# SoC_PS_500_501_502_MIO.net
KiCad netlist of a schematic drawn in Altium Designer
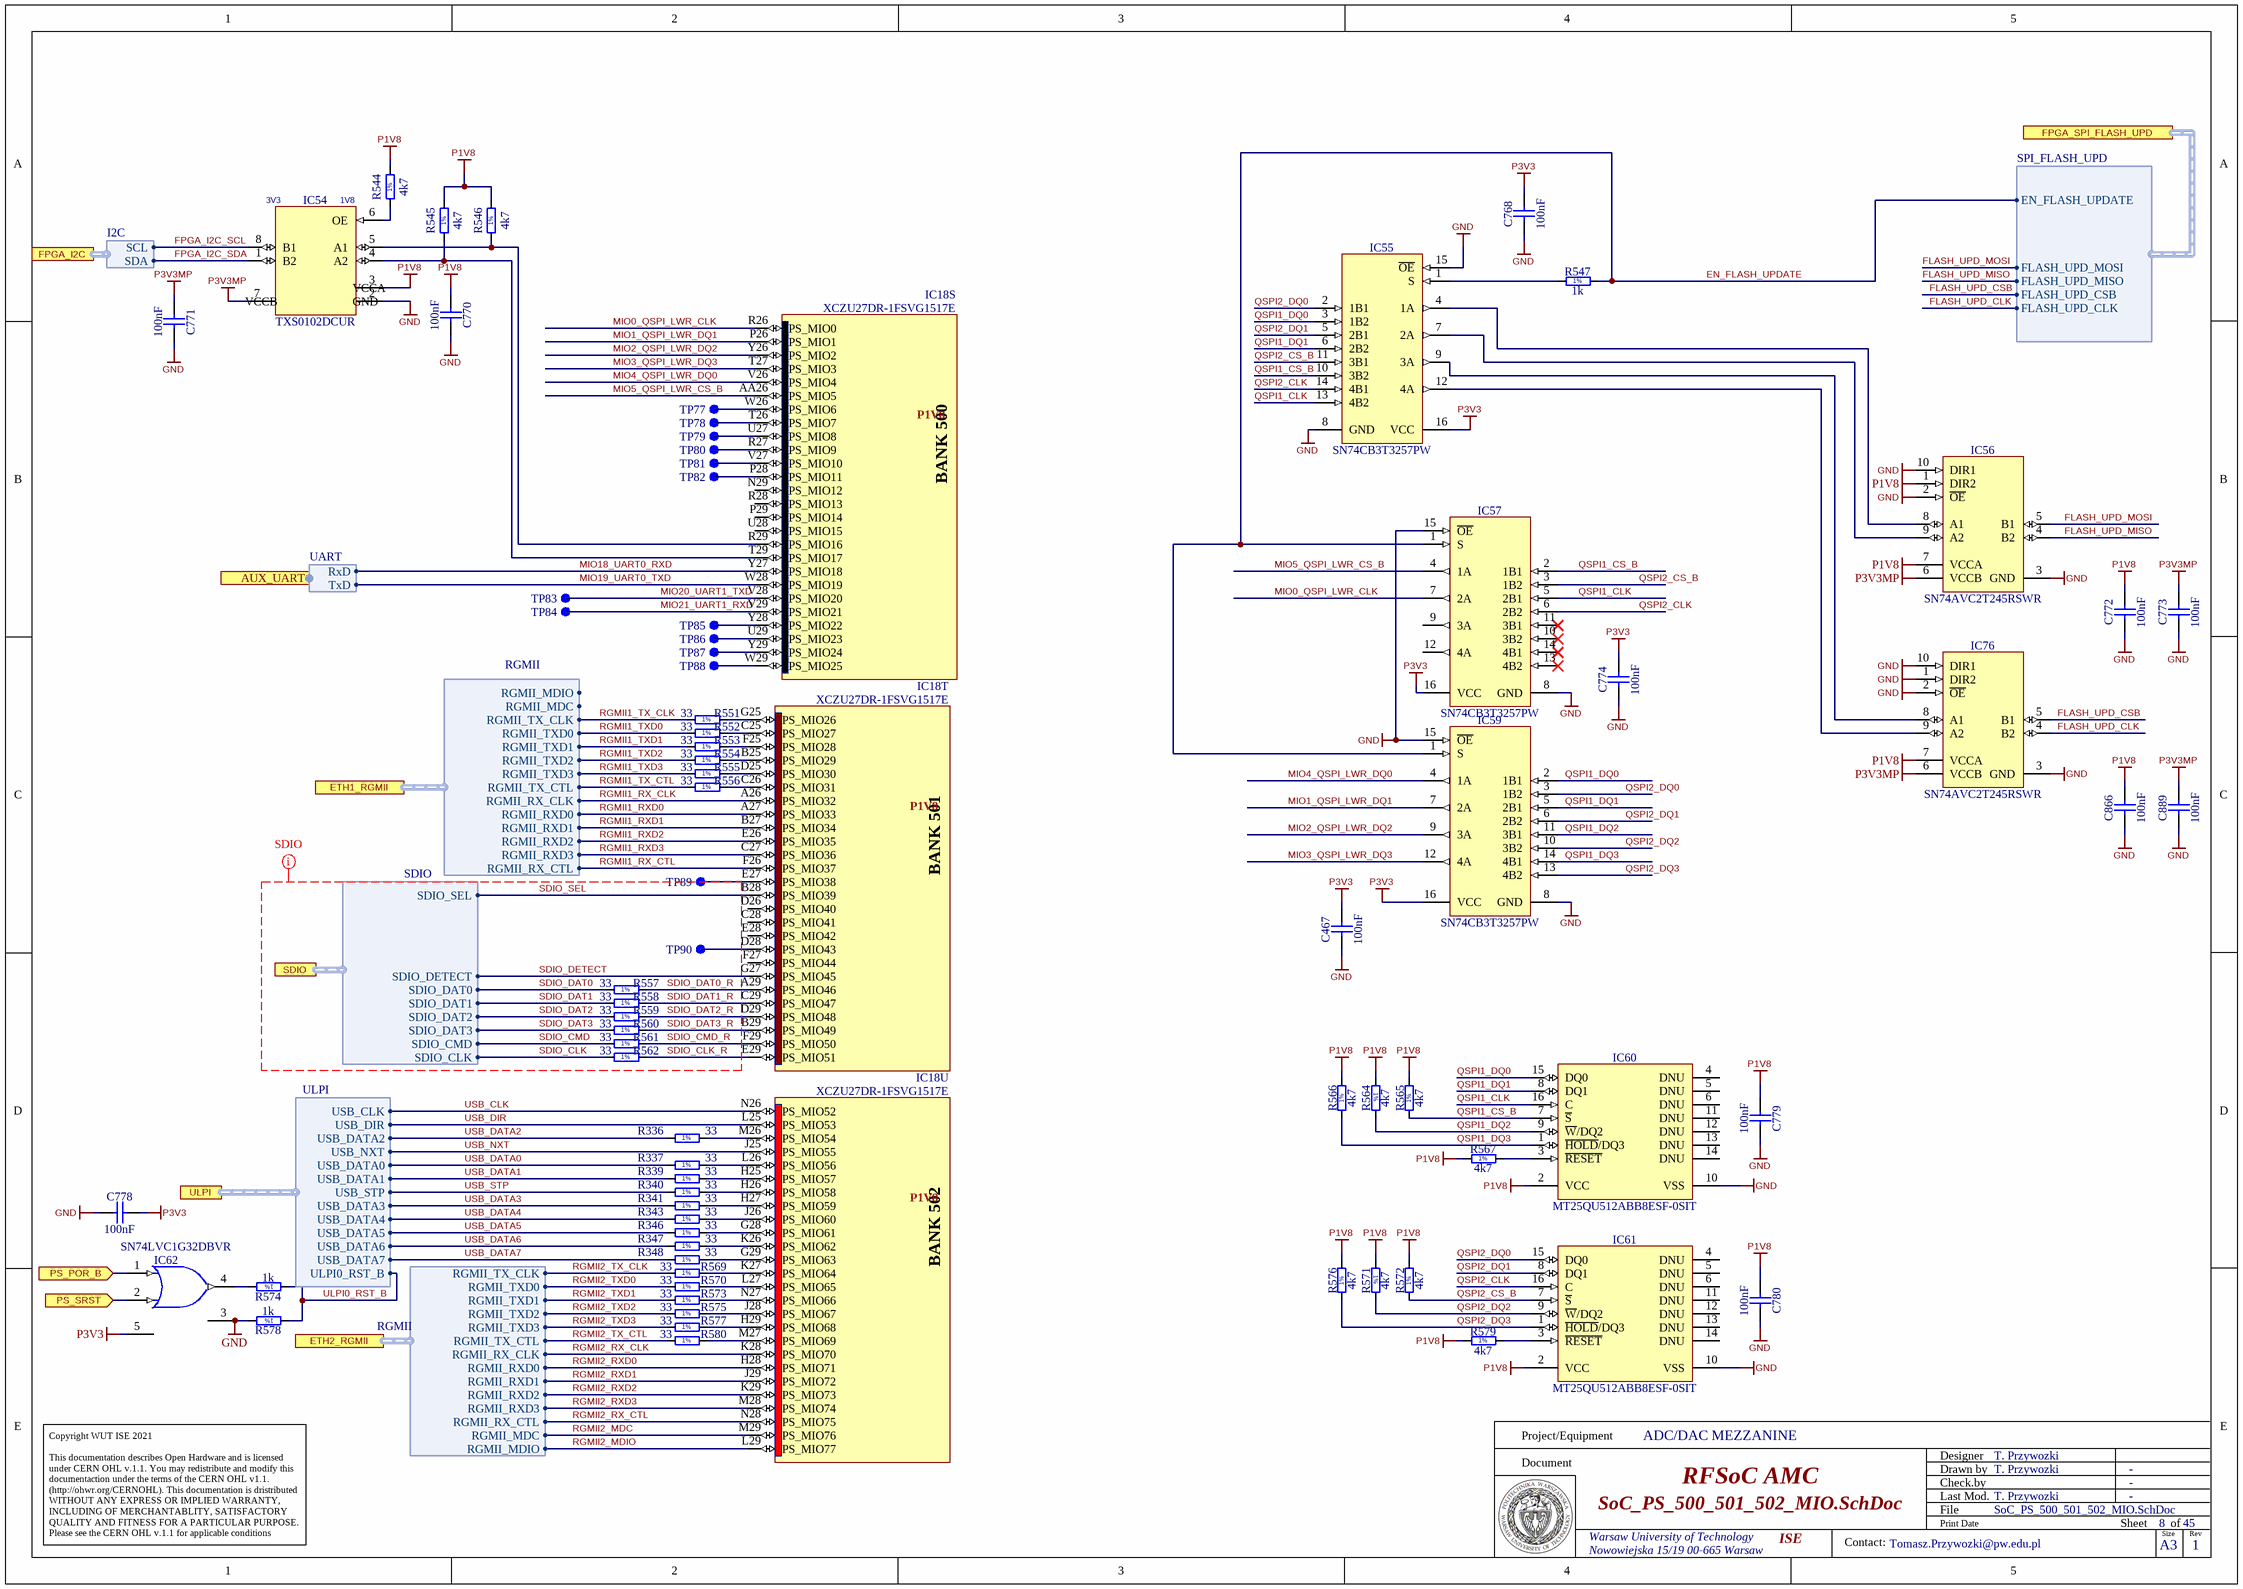
[diagram p0: SoC_PS_500_501_502_MIO.SchDoc]

(export (version "E")
  (design (tool "Eeschema 10.0.6"))
  (components
    (comp (ref "C467")
      (value "100nF")
      (footprint "CAPC0603X33N")
      (description "Non-polarised capacitor")
      (fields
        (field (name "MANUFACTURER PART NUMBER") "CC0201_100NF_6.3V_10%_X5R")
        (field (name "MANUFACTURER") "GENERIC")
        (field (name "AUTHOR") "CERN DEM JLC")
      )
      (libsource (lib "Capacitors") (part "Capacitor - non polarized"))
    )
    (comp (ref "C768")
      (value "100nF")
      (footprint "CAPC0603X33N")
      (description "Non-polarised capacitor")
      (fields
        (field (name "MANUFACTURER PART NUMBER") "CC0201_100NF_6.3V_10%_X5R")
        (field (name "MANUFACTURER") "GENERIC")
        (field (name "AUTHOR") "CERN DEM JLC")
      )
      (libsource (lib "Capacitors") (part "Capacitor - non polarized"))
    )
    (comp (ref "C770")
      (value "100nF")
      (footprint "CAPC0603X33N")
      (description "Non-polarised capacitor")
      (fields
        (field (name "MANUFACTURER PART NUMBER") "CC0201_100NF_6.3V_10%_X5R")
        (field (name "MANUFACTURER") "GENERIC")
        (field (name "AUTHOR") "CERN DEM JLC")
      )
      (libsource (lib "Capacitors") (part "Capacitor - non polarized"))
    )
    (comp (ref "C771")
      (value "100nF")
      (footprint "CAPC0603X33N")
      (description "Non-polarised capacitor")
      (fields
        (field (name "MANUFACTURER PART NUMBER") "CC0201_100NF_6.3V_10%_X5R")
        (field (name "MANUFACTURER") "GENERIC")
        (field (name "AUTHOR") "CERN DEM JLC")
      )
      (libsource (lib "Capacitors") (part "Capacitor - non polarized"))
    )
    (comp (ref "C772")
      (value "100nF")
      (footprint "CAPC0603X33N")
      (description "Non-polarised capacitor")
      (fields
        (field (name "MANUFACTURER PART NUMBER") "CC0201_100NF_6.3V_10%_X5R")
        (field (name "MANUFACTURER") "GENERIC")
        (field (name "AUTHOR") "CERN DEM JLC")
      )
      (libsource (lib "Capacitors") (part "Capacitor - non polarized"))
    )
    (comp (ref "C773")
      (value "100nF")
      (footprint "CAPC0603X33N")
      (description "Non-polarised capacitor")
      (fields
        (field (name "MANUFACTURER PART NUMBER") "CC0201_100NF_6.3V_10%_X5R")
        (field (name "MANUFACTURER") "GENERIC")
        (field (name "AUTHOR") "CERN DEM JLC")
      )
      (libsource (lib "Capacitors") (part "Capacitor - non polarized"))
    )
    (comp (ref "C774")
      (value "100nF")
      (footprint "CAPC0603X33N")
      (description "Non-polarised capacitor")
      (fields
        (field (name "MANUFACTURER PART NUMBER") "CC0201_100NF_6.3V_10%_X5R")
        (field (name "MANUFACTURER") "GENERIC")
        (field (name "AUTHOR") "CERN DEM JLC")
      )
      (libsource (lib "Capacitors") (part "Capacitor - non polarized"))
    )
    (comp (ref "C778")
      (value "100nF")
      (footprint "CAPC0603X33N")
      (description "Non-polarised capacitor")
      (fields
        (field (name "MANUFACTURER PART NUMBER") "CC0201_100NF_6.3V_10%_X5R")
        (field (name "MANUFACTURER") "GENERIC")
        (field (name "AUTHOR") "CERN DEM JLC")
      )
      (libsource (lib "Capacitors") (part "Capacitor - non polarized"))
    )
    (comp (ref "C779")
      (value "100nF")
      (footprint "CAPC0603X33N")
      (description "Non-polarised capacitor")
      (fields
        (field (name "MANUFACTURER PART NUMBER") "CC0201_100NF_6.3V_10%_X5R")
        (field (name "MANUFACTURER") "GENERIC")
        (field (name "AUTHOR") "CERN DEM JLC")
      )
      (libsource (lib "Capacitors") (part "Capacitor - non polarized"))
    )
    (comp (ref "C780")
      (value "100nF")
      (footprint "CAPC0603X33N")
      (description "Non-polarised capacitor")
      (fields
        (field (name "MANUFACTURER PART NUMBER") "CC0201_100NF_6.3V_10%_X5R")
        (field (name "MANUFACTURER") "GENERIC")
        (field (name "AUTHOR") "CERN DEM JLC")
      )
      (libsource (lib "Capacitors") (part "Capacitor - non polarized"))
    )
    (comp (ref "C866")
      (value "100nF")
      (footprint "CAPC0603X33N")
      (description "Non-polarised capacitor")
      (fields
        (field (name "MANUFACTURER PART NUMBER") "CC0201_100NF_6.3V_10%_X5R")
        (field (name "MANUFACTURER") "GENERIC")
        (field (name "AUTHOR") "CERN DEM JLC")
      )
      (libsource (lib "Capacitors") (part "Capacitor - non polarized"))
    )
    (comp (ref "C889")
      (value "100nF")
      (footprint "CAPC0603X33N")
      (description "Non-polarised capacitor")
      (fields
        (field (name "MANUFACTURER PART NUMBER") "CC0201_100NF_6.3V_10%_X5R")
        (field (name "MANUFACTURER") "GENERIC")
        (field (name "AUTHOR") "CERN DEM JLC")
      )
      (libsource (lib "Capacitors") (part "Capacitor - non polarized"))
    )
    (comp (ref "IC18")
      (value "XCZU27DR-1FSVG1517E")
      (footprint "XILINX_FSVG1517 (XCZU27DR)")
      (fields (field (name "MANUFACTURER") "XILINX") (field (name "AUTHOR") "CERN DEM MR"))
      (libsource (lib "ICs And Semiconductors") (part "XCZU27DR-1FSVG1517E"))
    )
    (comp (ref "IC54")
      (value "TXS0102DCUR")
      (footprint "SOP50P310X90-8N")
      (description "2-Bit Bidirectionnal Voltage-Level Translator for Open-Drain And Push-Pull Applications")
      (fields (field (name "MANUFACTURER") "TEXAS INSTRUMENTS") (field (name "AUTHOR") "CERN DEM JLC"))
      (libsource (lib "ICs And Semiconductors") (part "TXS0102DCU"))
    )
    (comp (ref "IC55")
      (value "SN74CB3T3257PW")
      (footprint "SOP65P640X120-16N")
      (description "4-BIT 1-OF-2 FET Multiplexer/Demultiplexer 2.5V/3.3V Low-Voltage Bus Switch 5V Tolerant Shifter")
      (fields (field (name "MANUFACTURER") "TEXAS INSTRUMENTS") (field (name "AUTHOR") "CERN DEM JLC"))
      (libsource (lib "ICs And Semiconductors") (part "743257"))
    )
    (comp (ref "IC56")
      (value "SN74AVC2T245RSWR")
      (footprint "QFN40P140X180X55-10N")
      (description "Dual-Bit Dual-Supply Bus Transceiver With Configurable Voltage Translation and 3-State Outputs")
      (fields (field (name "MANUFACTURER") "TEXAS INSTRUMENTS") (field (name "AUTHOR") "CERN DEM JLC"))
      (libsource (lib "ICs And Semiconductors") (part "742T245"))
    )
    (comp (ref "IC57")
      (value "SN74CB3T3257PW")
      (footprint "SOP65P640X120-16N")
      (description "4-BIT 1-OF-2 FET Multiplexer/Demultiplexer 2.5V/3.3V Low-Voltage Bus Switch 5V Tolerant Shifter")
      (fields (field (name "MANUFACTURER") "TEXAS INSTRUMENTS") (field (name "AUTHOR") "CERN DEM JLC"))
      (libsource (lib "") (part "743257_1"))
    )
    (comp (ref "IC59")
      (value "SN74CB3T3257PW")
      (footprint "SOP65P640X120-16N")
      (description "4-BIT 1-OF-2 FET Multiplexer/Demultiplexer 2.5V/3.3V Low-Voltage Bus Switch 5V Tolerant Shifter")
      (fields (field (name "MANUFACTURER") "TEXAS INSTRUMENTS") (field (name "AUTHOR") "CERN DEM JLC"))
      (libsource (lib "") (part "743257_1"))
    )
    (comp (ref "IC60")
      (value "MT25QU512ABB8ESF-0SIT")
      (footprint "SOIC127P1030X265-16N")
      (description "512Mbit (64MB), 1.8V, Multiple I/O Serial Flash Memory, Reset# & Hold# Pins")
      (fields (field (name "MANUFACTURER") "MICRON TECHNOLOGY") (field (name "AUTHOR") "CERN DEM MR"))
      (libsource (lib "ICs And Semiconductors") (part "MT25QU512ABB8ESF"))
    )
    (comp (ref "IC61")
      (value "MT25QU512ABB8ESF-0SIT")
      (footprint "SOIC127P1030X265-16N")
      (description "512Mbit (64MB), 1.8V, Multiple I/O Serial Flash Memory, Reset# & Hold# Pins")
      (fields (field (name "MANUFACTURER") "MICRON TECHNOLOGY") (field (name "AUTHOR") "CERN DEM MR"))
      (libsource (lib "ICs And Semiconductors") (part "MT25QU512ABB8ESF"))
    )
    (comp (ref "IC62")
      (value "SN74LVC1G32DBVR")
      (footprint "SOT95P280X145-5N")
      (description "Single 2-Input Positive-OR Gate")
      (fields (field (name "MANUFACTURER") "TEXAS INSTRUMENTS") (field (name "AUTHOR") "CERN DEM JLC"))
      (libsource (lib "ICs And Semiconductors") (part "741G32"))
    )
    (comp (ref "IC76")
      (value "SN74AVC2T245RSWR")
      (footprint "QFN40P140X180X55-10N")
      (description "Dual-Bit Dual-Supply Bus Transceiver With Configurable Voltage Translation and 3-State Outputs")
      (fields (field (name "MANUFACTURER") "TEXAS INSTRUMENTS") (field (name "AUTHOR") "CERN DEM JLC"))
      (libsource (lib "ICs And Semiconductors") (part "742T245"))
    )
    (comp (ref "R336")
      (value "33")
      (footprint "RESC1005X40N")
      (description "Resistor - 1%")
      (fields
        (field (name "MANUFACTURER PART NUMBER") "R0402_33R_1%_0.0625W_100PPM")
        (field (name "MANUFACTURER") "GENERIC")
        (field (name "AUTHOR") "CERN DEM JLC")
      )
      (libsource (lib "Resistors") (part "Resistor - 1%"))
    )
    (comp (ref "R337")
      (value "33")
      (footprint "RESC1005X40N")
      (description "Resistor - 1%")
      (fields
        (field (name "MANUFACTURER PART NUMBER") "R0402_33R_1%_0.0625W_100PPM")
        (field (name "MANUFACTURER") "GENERIC")
        (field (name "AUTHOR") "CERN DEM JLC")
      )
      (libsource (lib "Resistors") (part "Resistor - 1%"))
    )
    (comp (ref "R339")
      (value "33")
      (footprint "RESC1005X40N")
      (description "Resistor - 1%")
      (fields
        (field (name "MANUFACTURER PART NUMBER") "R0402_33R_1%_0.0625W_100PPM")
        (field (name "MANUFACTURER") "GENERIC")
        (field (name "AUTHOR") "CERN DEM JLC")
      )
      (libsource (lib "Resistors") (part "Resistor - 1%"))
    )
    (comp (ref "R340")
      (value "33")
      (footprint "RESC1005X40N")
      (description "Resistor - 1%")
      (fields
        (field (name "MANUFACTURER PART NUMBER") "R0402_33R_1%_0.0625W_100PPM")
        (field (name "MANUFACTURER") "GENERIC")
        (field (name "AUTHOR") "CERN DEM JLC")
      )
      (libsource (lib "Resistors") (part "Resistor - 1%"))
    )
    (comp (ref "R341")
      (value "33")
      (footprint "RESC1005X40N")
      (description "Resistor - 1%")
      (fields
        (field (name "MANUFACTURER PART NUMBER") "R0402_33R_1%_0.0625W_100PPM")
        (field (name "MANUFACTURER") "GENERIC")
        (field (name "AUTHOR") "CERN DEM JLC")
      )
      (libsource (lib "Resistors") (part "Resistor - 1%"))
    )
    (comp (ref "R343")
      (value "33")
      (footprint "RESC1005X40N")
      (description "Resistor - 1%")
      (fields
        (field (name "MANUFACTURER PART NUMBER") "R0402_33R_1%_0.0625W_100PPM")
        (field (name "MANUFACTURER") "GENERIC")
        (field (name "AUTHOR") "CERN DEM JLC")
      )
      (libsource (lib "Resistors") (part "Resistor - 1%"))
    )
    (comp (ref "R346")
      (value "33")
      (footprint "RESC1005X40N")
      (description "Resistor - 1%")
      (fields
        (field (name "MANUFACTURER PART NUMBER") "R0402_33R_1%_0.0625W_100PPM")
        (field (name "MANUFACTURER") "GENERIC")
        (field (name "AUTHOR") "CERN DEM JLC")
      )
      (libsource (lib "Resistors") (part "Resistor - 1%"))
    )
    (comp (ref "R347")
      (value "33")
      (footprint "RESC1005X40N")
      (description "Resistor - 1%")
      (fields
        (field (name "MANUFACTURER PART NUMBER") "R0402_33R_1%_0.0625W_100PPM")
        (field (name "MANUFACTURER") "GENERIC")
        (field (name "AUTHOR") "CERN DEM JLC")
      )
      (libsource (lib "Resistors") (part "Resistor - 1%"))
    )
    (comp (ref "R348")
      (value "33")
      (footprint "RESC1005X40N")
      (description "Resistor - 1%")
      (fields
        (field (name "MANUFACTURER PART NUMBER") "R0402_33R_1%_0.0625W_100PPM")
        (field (name "MANUFACTURER") "GENERIC")
        (field (name "AUTHOR") "CERN DEM JLC")
      )
      (libsource (lib "Resistors") (part "Resistor - 1%"))
    )
    (comp (ref "R544")
      (value "4k7")
      (footprint "RESC1005X40N")
      (description "Resistor - 1%")
      (fields
        (field (name "MANUFACTURER PART NUMBER") "R0402_4K7_1%_0.0625W_100PPM")
        (field (name "MANUFACTURER") "GENERIC")
        (field (name "AUTHOR") "CERN DEM JLC")
      )
      (libsource (lib "Resistors") (part "Resistor - 1%"))
    )
    (comp (ref "R545")
      (value "4k7")
      (footprint "RESC1005X40N")
      (description "Resistor - 1%")
      (fields
        (field (name "MANUFACTURER PART NUMBER") "R0402_4K7_1%_0.0625W_100PPM")
        (field (name "MANUFACTURER") "GENERIC")
        (field (name "AUTHOR") "CERN DEM JLC")
      )
      (libsource (lib "Resistors") (part "Resistor - 1%"))
    )
    (comp (ref "R546")
      (value "4k7")
      (footprint "RESC1005X40N")
      (description "Resistor - 1%")
      (fields
        (field (name "MANUFACTURER PART NUMBER") "R0402_4K7_1%_0.0625W_100PPM")
        (field (name "MANUFACTURER") "GENERIC")
        (field (name "AUTHOR") "CERN DEM JLC")
      )
      (libsource (lib "Resistors") (part "Resistor - 1%"))
    )
    (comp (ref "R547")
      (value "1k")
      (footprint "RESC1005X40N")
      (description "Resistor - 1%")
      (fields
        (field (name "MANUFACTURER PART NUMBER") "R0402_1K_1%_0.0625W_100PPM")
        (field (name "MANUFACTURER") "GENERIC")
        (field (name "AUTHOR") "CERN DEM JLC")
      )
      (libsource (lib "Resistors") (part "Resistor - 1%"))
    )
    (comp (ref "R551")
      (value "33")
      (footprint "RESC1005X40N")
      (description "Resistor - 1%")
      (fields
        (field (name "PART NUMBER") "R0402_33R_1%_0.0625W_100PPM")
        (field (name "POWER") "0.0625W")
        (field (name "AUTHOR") "CERN DEM JLC")
      )
      (libsource (lib "Resistors") (part "Resistor - 1%"))
    )
    (comp (ref "R552")
      (value "33")
      (footprint "RESC1005X40N")
      (description "Resistor - 1%")
      (fields
        (field (name "PART NUMBER") "R0402_33R_1%_0.0625W_100PPM")
        (field (name "POWER") "0.0625W")
        (field (name "AUTHOR") "CERN DEM JLC")
      )
      (libsource (lib "Resistors") (part "Resistor - 1%"))
    )
    (comp (ref "R553")
      (value "33")
      (footprint "RESC1005X40N")
      (description "Resistor - 1%")
      (fields
        (field (name "PART NUMBER") "R0402_33R_1%_0.0625W_100PPM")
        (field (name "POWER") "0.0625W")
        (field (name "AUTHOR") "CERN DEM JLC")
      )
      (libsource (lib "Resistors") (part "Resistor - 1%"))
    )
    (comp (ref "R554")
      (value "33")
      (footprint "RESC1005X40N")
      (description "Resistor - 1%")
      (fields
        (field (name "PART NUMBER") "R0402_33R_1%_0.0625W_100PPM")
        (field (name "POWER") "0.0625W")
        (field (name "AUTHOR") "CERN DEM JLC")
      )
      (libsource (lib "Resistors") (part "Resistor - 1%"))
    )
    (comp (ref "R555")
      (value "33")
      (footprint "RESC1005X40N")
      (description "Resistor - 1%")
      (fields
        (field (name "PART NUMBER") "R0402_33R_1%_0.0625W_100PPM")
        (field (name "POWER") "0.0625W")
        (field (name "AUTHOR") "CERN DEM JLC")
      )
      (libsource (lib "Resistors") (part "Resistor - 1%"))
    )
    (comp (ref "R556")
      (value "33")
      (footprint "RESC1005X40N")
      (description "Resistor - 1%")
      (fields
        (field (name "PART NUMBER") "R0402_33R_1%_0.0625W_100PPM")
        (field (name "POWER") "0.0625W")
        (field (name "AUTHOR") "CERN DEM JLC")
      )
      (libsource (lib "Resistors") (part "Resistor - 1%"))
    )
    (comp (ref "R557")
      (value "33")
      (footprint "RESC1005X40N")
      (description "Resistor - 1%")
      (fields
        (field (name "PART NUMBER") "R0402_33R_1%_0.0625W_100PPM")
        (field (name "POWER") "0.0625W")
        (field (name "AUTHOR") "CERN DEM JLC")
      )
      (libsource (lib "Resistors") (part "Resistor - 1%"))
    )
    (comp (ref "R558")
      (value "33")
      (footprint "RESC1005X40N")
      (description "Resistor - 1%")
      (fields
        (field (name "PART NUMBER") "R0402_33R_1%_0.0625W_100PPM")
        (field (name "POWER") "0.0625W")
        (field (name "AUTHOR") "CERN DEM JLC")
      )
      (libsource (lib "Resistors") (part "Resistor - 1%"))
    )
    (comp (ref "R559")
      (value "33")
      (footprint "RESC1005X40N")
      (description "Resistor - 1%")
      (fields
        (field (name "PART NUMBER") "R0402_33R_1%_0.0625W_100PPM")
        (field (name "POWER") "0.0625W")
        (field (name "AUTHOR") "CERN DEM JLC")
      )
      (libsource (lib "Resistors") (part "Resistor - 1%"))
    )
    (comp (ref "R560")
      (value "33")
      (footprint "RESC1005X40N")
      (description "Resistor - 1%")
      (fields
        (field (name "PART NUMBER") "R0402_33R_1%_0.0625W_100PPM")
        (field (name "POWER") "0.0625W")
        (field (name "AUTHOR") "CERN DEM JLC")
      )
      (libsource (lib "Resistors") (part "Resistor - 1%"))
    )
    (comp (ref "R561")
      (value "33")
      (footprint "RESC1005X40N")
      (description "Resistor - 1%")
      (fields
        (field (name "PART NUMBER") "R0402_33R_1%_0.0625W_100PPM")
        (field (name "POWER") "0.0625W")
        (field (name "AUTHOR") "CERN DEM JLC")
      )
      (libsource (lib "Resistors") (part "Resistor - 1%"))
    )
    (comp (ref "R562")
      (value "33")
      (footprint "RESC1005X40N")
      (description "Resistor - 1%")
      (fields
        (field (name "PART NUMBER") "R0402_33R_1%_0.0625W_100PPM")
        (field (name "POWER") "0.0625W")
        (field (name "AUTHOR") "CERN DEM JLC")
      )
      (libsource (lib "Resistors") (part "Resistor - 1%"))
    )
    (comp (ref "R564")
      (value "4k7")
      (footprint "RESC1005X40N")
      (description "Resistor - 1%")
      (fields
        (field (name "MANUFACTURER PART NUMBER") "R0402_4K7_1%_0.0625W_100PPM")
        (field (name "MANUFACTURER") "GENERIC")
        (field (name "AUTHOR") "CERN DEM JLC")
      )
      (libsource (lib "Resistors") (part "Resistor - 1%"))
    )
    (comp (ref "R565")
      (value "4k7")
      (footprint "RESC1005X40N")
      (description "Resistor - 1%")
      (fields
        (field (name "MANUFACTURER PART NUMBER") "R0402_4K7_1%_0.0625W_100PPM")
        (field (name "MANUFACTURER") "GENERIC")
        (field (name "AUTHOR") "CERN DEM JLC")
      )
      (libsource (lib "Resistors") (part "Resistor - 1%"))
    )
    (comp (ref "R566")
      (value "4k7")
      (footprint "RESC1005X40N")
      (description "Resistor - 1%")
      (fields
        (field (name "MANUFACTURER PART NUMBER") "R0402_4K7_1%_0.0625W_100PPM")
        (field (name "MANUFACTURER") "GENERIC")
        (field (name "AUTHOR") "CERN DEM JLC")
      )
      (libsource (lib "Resistors") (part "Resistor - 1%"))
    )
    (comp (ref "R567")
      (value "4k7")
      (footprint "RESC1005X40N")
      (description "Resistor - 1%")
      (fields
        (field (name "MANUFACTURER PART NUMBER") "R0402_4K7_1%_0.0625W_100PPM")
        (field (name "MANUFACTURER") "GENERIC")
        (field (name "AUTHOR") "CERN DEM JLC")
      )
      (libsource (lib "Resistors") (part "Resistor - 1%"))
    )
    (comp (ref "R569")
      (value "33")
      (footprint "RESC1005X40N")
      (description "Resistor - 1%")
      (fields
        (field (name "PART NUMBER") "R0402_33R_1%_0.0625W_100PPM")
        (field (name "POWER") "0.0625W")
        (field (name "AUTHOR") "CERN DEM JLC")
      )
      (libsource (lib "Resistors") (part "Resistor - 1%"))
    )
    (comp (ref "R570")
      (value "33")
      (footprint "RESC1005X40N")
      (description "Resistor - 1%")
      (fields
        (field (name "PART NUMBER") "R0402_33R_1%_0.0625W_100PPM")
        (field (name "POWER") "0.0625W")
        (field (name "AUTHOR") "CERN DEM JLC")
      )
      (libsource (lib "Resistors") (part "Resistor - 1%"))
    )
    (comp (ref "R571")
      (value "4k7")
      (footprint "RESC1005X40N")
      (description "Resistor - 1%")
      (fields
        (field (name "MANUFACTURER PART NUMBER") "R0402_4K7_1%_0.0625W_100PPM")
        (field (name "MANUFACTURER") "GENERIC")
        (field (name "AUTHOR") "CERN DEM JLC")
      )
      (libsource (lib "Resistors") (part "Resistor - 1%"))
    )
    (comp (ref "R572")
      (value "4k7")
      (footprint "RESC1005X40N")
      (description "Resistor - 1%")
      (fields
        (field (name "MANUFACTURER PART NUMBER") "R0402_4K7_1%_0.0625W_100PPM")
        (field (name "MANUFACTURER") "GENERIC")
        (field (name "AUTHOR") "CERN DEM JLC")
      )
      (libsource (lib "Resistors") (part "Resistor - 1%"))
    )
    (comp (ref "R573")
      (value "33")
      (footprint "RESC1005X40N")
      (description "Resistor - 1%")
      (fields
        (field (name "PART NUMBER") "R0402_33R_1%_0.0625W_100PPM")
        (field (name "POWER") "0.0625W")
        (field (name "AUTHOR") "CERN DEM JLC")
      )
      (libsource (lib "Resistors") (part "Resistor - 1%"))
    )
    (comp (ref "R574")
      (value "1k")
      (footprint "RESC1005X40N")
      (description "Resistor - 1%")
      (fields
        (field (name "PART NUMBER") "R0402_1K_1%_0.0625W_100PPM")
        (field (name "POWER") "0.0625W")
        (field (name "AUTHOR") "CERN DEM JLC")
      )
      (libsource (lib "Resistors") (part "Resistor - 1%"))
    )
    (comp (ref "R575")
      (value "33")
      (footprint "RESC1005X40N")
      (description "Resistor - 1%")
      (fields
        (field (name "PART NUMBER") "R0402_33R_1%_0.0625W_100PPM")
        (field (name "POWER") "0.0625W")
        (field (name "AUTHOR") "CERN DEM JLC")
      )
      (libsource (lib "Resistors") (part "Resistor - 1%"))
    )
    (comp (ref "R576")
      (value "4k7")
      (footprint "RESC1005X40N")
      (description "Resistor - 1%")
      (fields
        (field (name "MANUFACTURER PART NUMBER") "R0402_4K7_1%_0.0625W_100PPM")
        (field (name "MANUFACTURER") "GENERIC")
        (field (name "AUTHOR") "CERN DEM JLC")
      )
      (libsource (lib "Resistors") (part "Resistor - 1%"))
    )
    (comp (ref "R577")
      (value "33")
      (footprint "RESC1005X40N")
      (description "Resistor - 1%")
      (fields
        (field (name "PART NUMBER") "R0402_33R_1%_0.0625W_100PPM")
        (field (name "POWER") "0.0625W")
        (field (name "AUTHOR") "CERN DEM JLC")
      )
      (libsource (lib "Resistors") (part "Resistor - 1%"))
    )
    (comp (ref "R578")
      (value "1k")
      (footprint "RESC1005X40N")
      (description "Resistor - 1%")
      (fields
        (field (name "PART NUMBER") "R0402_1K_1%_0.0625W_100PPM")
        (field (name "POWER") "0.0625W")
        (field (name "AUTHOR") "CERN DEM JLC")
      )
      (libsource (lib "Resistors") (part "Resistor - 1%"))
    )
    (comp (ref "R579")
      (value "4k7")
      (footprint "RESC1005X40N")
      (description "Resistor - 1%")
      (fields
        (field (name "MANUFACTURER PART NUMBER") "R0402_4K7_1%_0.0625W_100PPM")
        (field (name "MANUFACTURER") "GENERIC")
        (field (name "AUTHOR") "CERN DEM JLC")
      )
      (libsource (lib "Resistors") (part "Resistor - 1%"))
    )
    (comp (ref "R580")
      (value "33")
      (footprint "RESC1005X40N")
      (description "Resistor - 1%")
      (fields
        (field (name "PART NUMBER") "R0402_33R_1%_0.0625W_100PPM")
        (field (name "POWER") "0.0625W")
        (field (name "AUTHOR") "CERN DEM JLC")
      )
      (libsource (lib "Resistors") (part "Resistor - 1%"))
    )
    (comp (ref "TP77")
      (value "SMD Pad")
      (footprint "C100")
      (description "Through Hole Pad")
      (fields (field (name "PART NUMBER") "SMD_PAD_D1MM") (field (name "AUTHOR") "CERN DEM JLC"))
      (libsource (lib "Eletro-mechanical") (part "Single SMD Pad (Round)"))
    )
    (comp (ref "TP78")
      (value "SMD Pad")
      (footprint "C100")
      (description "Through Hole Pad")
      (fields (field (name "PART NUMBER") "SMD_PAD_D1MM") (field (name "AUTHOR") "CERN DEM JLC"))
      (libsource (lib "Eletro-mechanical") (part "Single SMD Pad (Round)"))
    )
    (comp (ref "TP79")
      (value "SMD Pad")
      (footprint "C100")
      (description "Through Hole Pad")
      (fields (field (name "PART NUMBER") "SMD_PAD_D1MM") (field (name "AUTHOR") "CERN DEM JLC"))
      (libsource (lib "Eletro-mechanical") (part "Single SMD Pad (Round)"))
    )
    (comp (ref "TP80")
      (value "SMD Pad")
      (footprint "C100")
      (description "Through Hole Pad")
      (fields (field (name "PART NUMBER") "SMD_PAD_D1MM") (field (name "AUTHOR") "CERN DEM JLC"))
      (libsource (lib "Eletro-mechanical") (part "Single SMD Pad (Round)"))
    )
    (comp (ref "TP81")
      (value "SMD Pad")
      (footprint "C100")
      (description "Through Hole Pad")
      (fields (field (name "PART NUMBER") "SMD_PAD_D1MM") (field (name "AUTHOR") "CERN DEM JLC"))
      (libsource (lib "Eletro-mechanical") (part "Single SMD Pad (Round)"))
    )
    (comp (ref "TP82")
      (value "SMD Pad")
      (footprint "C100")
      (description "Through Hole Pad")
      (fields (field (name "PART NUMBER") "SMD_PAD_D1MM") (field (name "AUTHOR") "CERN DEM JLC"))
      (libsource (lib "Eletro-mechanical") (part "Single SMD Pad (Round)"))
    )
    (comp (ref "TP83")
      (value "SMD Pad")
      (footprint "C100")
      (description "Through Hole Pad")
      (fields (field (name "PART NUMBER") "SMD_PAD_D1MM") (field (name "AUTHOR") "CERN DEM JLC"))
      (libsource (lib "Eletro-mechanical") (part "Single SMD Pad (Round)"))
    )
    (comp (ref "TP84")
      (value "SMD Pad")
      (footprint "C100")
      (description "Through Hole Pad")
      (fields (field (name "PART NUMBER") "SMD_PAD_D1MM") (field (name "AUTHOR") "CERN DEM JLC"))
      (libsource (lib "Eletro-mechanical") (part "Single SMD Pad (Round)"))
    )
    (comp (ref "TP85")
      (value "SMD Pad")
      (footprint "C100")
      (description "Through Hole Pad")
      (fields (field (name "PART NUMBER") "SMD_PAD_D1MM") (field (name "AUTHOR") "CERN DEM JLC"))
      (libsource (lib "Eletro-mechanical") (part "Single SMD Pad (Round)"))
    )
    (comp (ref "TP86")
      (value "SMD Pad")
      (footprint "C100")
      (description "Through Hole Pad")
      (fields (field (name "PART NUMBER") "SMD_PAD_D1MM") (field (name "AUTHOR") "CERN DEM JLC"))
      (libsource (lib "Eletro-mechanical") (part "Single SMD Pad (Round)"))
    )
    (comp (ref "TP87")
      (value "SMD Pad")
      (footprint "C100")
      (description "Through Hole Pad")
      (fields (field (name "PART NUMBER") "SMD_PAD_D1MM") (field (name "AUTHOR") "CERN DEM JLC"))
      (libsource (lib "Eletro-mechanical") (part "Single SMD Pad (Round)"))
    )
    (comp (ref "TP88")
      (value "SMD Pad")
      (footprint "C100")
      (description "Through Hole Pad")
      (fields (field (name "PART NUMBER") "SMD_PAD_D1MM") (field (name "AUTHOR") "CERN DEM JLC"))
      (libsource (lib "Eletro-mechanical") (part "Single SMD Pad (Round)"))
    )
    (comp (ref "TP89")
      (value "SMD Pad")
      (footprint "C100")
      (description "Through Hole Pad")
      (fields (field (name "PART NUMBER") "SMD_PAD_D1MM") (field (name "AUTHOR") "CERN DEM JLC"))
      (libsource (lib "Eletro-mechanical") (part "Single SMD Pad (Round)"))
    )
    (comp (ref "TP90")
      (value "SMD Pad")
      (footprint "C100")
      (description "Through Hole Pad")
      (fields (field (name "PART NUMBER") "SMD_PAD_D1MM") (field (name "AUTHOR") "CERN DEM JLC"))
      (libsource (lib "Eletro-mechanical") (part "Single SMD Pad (Round)"))
    )
  )
  (nets
    (net (code "7") (name "/EN_FLASH_UPDATE") (class "Default")
      (node (ref "IC57") (pin "1") (pinfunction "S_1") (pintype "input"))
      (node (ref "IC59") (pin "1") (pinfunction "S_1") (pintype "input"))
      (node (ref "R547") (pin "2") (pinfunction "2_2") (pintype "passive"))
    )
    (net (code "8") (name "/FLASH_UPD_CLK") (class "Default")
      (node (ref "IC76") (pin "4") (pinfunction "B2_4") (pintype "bidirectional"))
    )
    (net (code "9") (name "/FLASH_UPD_CSB") (class "Default")
      (node (ref "IC76") (pin "5") (pinfunction "B1_5") (pintype "bidirectional"))
    )
    (net (code "10") (name "/FLASH_UPD_MISO") (class "Default")
      (node (ref "IC56") (pin "4") (pinfunction "B2_4") (pintype "bidirectional"))
    )
    (net (code "11") (name "/FLASH_UPD_MOSI") (class "Default")
      (node (ref "IC56") (pin "5") (pinfunction "B1_5") (pintype "bidirectional"))
    )
    (net (code "12") (name "/FPGA_I2C_SCL") (class "Default")
      (node (ref "IC54") (pin "8") (pinfunction "B1_8") (pintype "bidirectional"))
    )
    (net (code "13") (name "/FPGA_I2C_SDA") (class "Default")
      (node (ref "IC54") (pin "1") (pinfunction "B2_1") (pintype "bidirectional"))
    )
    (net (code "14") (name "/MIO0_QSPI_LWR_CLK") (class "Default")
      (node (ref "IC18") (pin "R26") (pinfunction "PS_MIO0_R26") (pintype "bidirectional"))
      (node (ref "IC57") (pin "7") (pinfunction "2A_7") (pintype "output"))
    )
    (net (code "15") (name "/MIO1_QSPI_LWR_DQ1") (class "Default")
      (node (ref "IC18") (pin "P26") (pinfunction "PS_MIO1_P26") (pintype "bidirectional"))
      (node (ref "IC59") (pin "7") (pinfunction "2A_7") (pintype "output"))
    )
    (net (code "16") (name "/MIO2_QSPI_LWR_DQ2") (class "Default")
      (node (ref "IC18") (pin "Y26") (pinfunction "PS_MIO2_Y26") (pintype "bidirectional"))
      (node (ref "IC59") (pin "9") (pinfunction "3A_9") (pintype "output"))
    )
    (net (code "17") (name "/MIO3_QSPI_LWR_DQ3") (class "Default")
      (node (ref "IC18") (pin "T27") (pinfunction "PS_MIO3_T27") (pintype "bidirectional"))
      (node (ref "IC59") (pin "12") (pinfunction "4A_12") (pintype "output"))
    )
    (net (code "18") (name "/MIO4_QSPI_LWR_DQ0") (class "Default")
      (node (ref "IC18") (pin "V26") (pinfunction "PS_MIO4_V26") (pintype "bidirectional"))
      (node (ref "IC59") (pin "4") (pinfunction "1A_4") (pintype "output"))
    )
    (net (code "19") (name "/MIO5_QSPI_LWR_CS_B") (class "Default")
      (node (ref "IC18") (pin "AA26") (pinfunction "PS_MIO5_AA26") (pintype "bidirectional"))
      (node (ref "IC57") (pin "4") (pinfunction "1A_4") (pintype "output"))
    )
    (net (code "20") (name "/MIO18_UART0_RXD") (class "Default")
      (node (ref "IC18") (pin "Y27") (pinfunction "PS_MIO18_Y27") (pintype "bidirectional"))
    )
    (net (code "21") (name "/MIO19_UART0_TXD") (class "Default")
      (node (ref "IC18") (pin "W28") (pinfunction "PS_MIO19_W28") (pintype "bidirectional"))
    )
    (net (code "22") (name "/MIO20_UART1_TXD") (class "Default")
      (node (ref "IC18") (pin "V28") (pinfunction "PS_MIO20_V28") (pintype "bidirectional"))
      (node (ref "TP83") (pin "1") (pinfunction "1_1") (pintype "bidirectional"))
    )
    (net (code "23") (name "/MIO21_UART1_RXD") (class "Default")
      (node (ref "IC18") (pin "V29") (pinfunction "PS_MIO21_V29") (pintype "bidirectional"))
      (node (ref "TP84") (pin "1") (pinfunction "1_1") (pintype "bidirectional"))
    )
    (net (code "24") (name "/PS_POR_B") (class "Default")
      (node (ref "IC62") (pin "1") (pinfunction "A_1") (pintype "input"))
    )
    (net (code "25") (name "/PS_SRST") (class "Default")
      (node (ref "IC62") (pin "2") (pinfunction "B_2") (pintype "input"))
    )
    (net (code "26") (name "/QSPI1_CLK") (class "Default")
      (node (ref "IC55") (pin "13") (pinfunction "4B2_13") (pintype "input"))
      (node (ref "IC57") (pin "5") (pinfunction "2B1_5") (pintype "input"))
      (node (ref "IC60") (pin "16") (pinfunction "C_16") (pintype "input"))
    )
    (net (code "27") (name "/QSPI1_CS_B") (class "Default")
      (node (ref "IC55") (pin "10") (pinfunction "3B2_10") (pintype "input"))
      (node (ref "IC57") (pin "2") (pinfunction "1B1_2") (pintype "input"))
      (node (ref "IC60") (pin "7") (pinfunction "~{S}_7") (pintype "input"))
      (node (ref "R565") (pin "1") (pinfunction "1_1") (pintype "passive"))
    )
    (net (code "28") (name "/QSPI1_DQ0") (class "Default")
      (node (ref "IC55") (pin "3") (pinfunction "1B2_3") (pintype "input"))
      (node (ref "IC59") (pin "2") (pinfunction "1B1_2") (pintype "input"))
      (node (ref "IC60") (pin "15") (pinfunction "DQ0_15") (pintype "bidirectional"))
    )
    (net (code "29") (name "/QSPI1_DQ1") (class "Default")
      (node (ref "IC55") (pin "6") (pinfunction "2B2_6") (pintype "input"))
      (node (ref "IC59") (pin "5") (pinfunction "2B1_5") (pintype "input"))
      (node (ref "IC60") (pin "8") (pinfunction "DQ1_8") (pintype "bidirectional"))
    )
    (net (code "30") (name "/QSPI1_DQ2") (class "Default")
      (node (ref "IC59") (pin "11") (pinfunction "3B1_11") (pintype "input"))
      (node (ref "IC60") (pin "9") (pinfunction "~{W}/DQ2_9") (pintype "bidirectional"))
      (node (ref "R564") (pin "2") (pinfunction "2_2") (pintype "passive"))
    )
    (net (code "31") (name "/QSPI1_DQ3") (class "Default")
      (node (ref "IC59") (pin "14") (pinfunction "4B1_14") (pintype "input"))
      (node (ref "IC60") (pin "1") (pinfunction "~{HOLD}/DQ3_1") (pintype "bidirectional"))
      (node (ref "R566") (pin "1") (pinfunction "1_1") (pintype "passive"))
    )
    (net (code "32") (name "/QSPI2_CLK") (class "Default")
      (node (ref "IC55") (pin "14") (pinfunction "4B1_14") (pintype "input"))
      (node (ref "IC57") (pin "6") (pinfunction "2B2_6") (pintype "input"))
      (node (ref "IC61") (pin "16") (pinfunction "C_16") (pintype "input"))
    )
    (net (code "33") (name "/QSPI2_CS_B") (class "Default")
      (node (ref "IC55") (pin "11") (pinfunction "3B1_11") (pintype "input"))
      (node (ref "IC57") (pin "3") (pinfunction "1B2_3") (pintype "input"))
      (node (ref "IC61") (pin "7") (pinfunction "~{S}_7") (pintype "input"))
      (node (ref "R572") (pin "1") (pinfunction "1_1") (pintype "passive"))
    )
    (net (code "34") (name "/QSPI2_DQ0") (class "Default")
      (node (ref "IC55") (pin "2") (pinfunction "1B1_2") (pintype "input"))
      (node (ref "IC59") (pin "3") (pinfunction "1B2_3") (pintype "input"))
      (node (ref "IC61") (pin "15") (pinfunction "DQ0_15") (pintype "bidirectional"))
    )
    (net (code "35") (name "/QSPI2_DQ1") (class "Default")
      (node (ref "IC55") (pin "5") (pinfunction "2B1_5") (pintype "input"))
      (node (ref "IC59") (pin "6") (pinfunction "2B2_6") (pintype "input"))
      (node (ref "IC61") (pin "8") (pinfunction "DQ1_8") (pintype "bidirectional"))
    )
    (net (code "36") (name "/QSPI2_DQ2") (class "Default")
      (node (ref "IC59") (pin "10") (pinfunction "3B2_10") (pintype "input"))
      (node (ref "IC61") (pin "9") (pinfunction "~{W}/DQ2_9") (pintype "bidirectional"))
      (node (ref "R571") (pin "2") (pinfunction "2_2") (pintype "passive"))
    )
    (net (code "37") (name "/QSPI2_DQ3") (class "Default")
      (node (ref "IC59") (pin "13") (pinfunction "4B2_13") (pintype "input"))
      (node (ref "IC61") (pin "1") (pinfunction "~{HOLD}/DQ3_1") (pintype "bidirectional"))
      (node (ref "R576") (pin "1") (pinfunction "1_1") (pintype "passive"))
    )
    (net (code "38") (name "/RGMII1_RXD0") (class "Default")
      (node (ref "IC18") (pin "A27") (pinfunction "PS_MIO33_A27") (pintype "bidirectional"))
    )
    (net (code "39") (name "/RGMII1_RXD1") (class "Default")
      (node (ref "IC18") (pin "B27") (pinfunction "PS_MIO34_B27") (pintype "bidirectional"))
    )
    (net (code "40") (name "/RGMII1_RXD2") (class "Default")
      (node (ref "IC18") (pin "E26") (pinfunction "PS_MIO35_E26") (pintype "bidirectional"))
    )
    (net (code "41") (name "/RGMII1_RXD3") (class "Default")
      (node (ref "IC18") (pin "C27") (pinfunction "PS_MIO36_C27") (pintype "bidirectional"))
    )
    (net (code "42") (name "/RGMII1_RX_CLK") (class "Default")
      (node (ref "IC18") (pin "A26") (pinfunction "PS_MIO32_A26") (pintype "bidirectional"))
    )
    (net (code "43") (name "/RGMII1_RX_CTL") (class "Default")
      (node (ref "IC18") (pin "F26") (pinfunction "PS_MIO37_F26") (pintype "bidirectional"))
    )
    (net (code "44") (name "/RGMII1_TXD0") (class "Default")
      (node (ref "R552") (pin "1") (pinfunction "1_1") (pintype "passive"))
    )
    (net (code "45") (name "/RGMII1_TXD1") (class "Default")
      (node (ref "R553") (pin "1") (pinfunction "1_1") (pintype "passive"))
    )
    (net (code "46") (name "/RGMII1_TXD2") (class "Default")
      (node (ref "R554") (pin "1") (pinfunction "1_1") (pintype "passive"))
    )
    (net (code "47") (name "/RGMII1_TXD3") (class "Default")
      (node (ref "R555") (pin "1") (pinfunction "1_1") (pintype "passive"))
    )
    (net (code "48") (name "/RGMII1_TX_CLK") (class "Default")
      (node (ref "R551") (pin "1") (pinfunction "1_1") (pintype "passive"))
    )
    (net (code "49") (name "/RGMII1_TX_CTL") (class "Default")
      (node (ref "R556") (pin "1") (pinfunction "1_1") (pintype "passive"))
    )
    (net (code "50") (name "/RGMII2_MDC") (class "Default")
      (node (ref "IC18") (pin "M29") (pinfunction "PS_MIO76_M29") (pintype "bidirectional"))
    )
    (net (code "51") (name "/RGMII2_MDIO") (class "Default")
      (node (ref "IC18") (pin "L29") (pinfunction "PS_MIO77_L29") (pintype "bidirectional"))
    )
    (net (code "52") (name "/RGMII2_RXD0") (class "Default")
      (node (ref "IC18") (pin "H28") (pinfunction "PS_MIO71_H28") (pintype "bidirectional"))
    )
    (net (code "53") (name "/RGMII2_RXD1") (class "Default")
      (node (ref "IC18") (pin "J29") (pinfunction "PS_MIO72_J29") (pintype "bidirectional"))
    )
    (net (code "54") (name "/RGMII2_RXD2") (class "Default")
      (node (ref "IC18") (pin "K29") (pinfunction "PS_MIO73_K29") (pintype "bidirectional"))
    )
    (net (code "55") (name "/RGMII2_RXD3") (class "Default")
      (node (ref "IC18") (pin "M28") (pinfunction "PS_MIO74_M28") (pintype "bidirectional"))
    )
    (net (code "56") (name "/RGMII2_RX_CLK") (class "Default")
      (node (ref "IC18") (pin "K28") (pinfunction "PS_MIO70_K28") (pintype "bidirectional"))
    )
    (net (code "57") (name "/RGMII2_RX_CTL") (class "Default")
      (node (ref "IC18") (pin "N28") (pinfunction "PS_MIO75_N28") (pintype "bidirectional"))
    )
    (net (code "58") (name "/RGMII2_TXD0") (class "Default")
      (node (ref "R570") (pin "1") (pinfunction "1_1") (pintype "passive"))
    )
    (net (code "59") (name "/RGMII2_TXD1") (class "Default")
      (node (ref "R573") (pin "1") (pinfunction "1_1") (pintype "passive"))
    )
    (net (code "60") (name "/RGMII2_TXD2") (class "Default")
      (node (ref "R575") (pin "1") (pinfunction "1_1") (pintype "passive"))
    )
    (net (code "61") (name "/RGMII2_TXD3") (class "Default")
      (node (ref "R577") (pin "1") (pinfunction "1_1") (pintype "passive"))
    )
    (net (code "62") (name "/RGMII2_TX_CLK") (class "Default")
      (node (ref "R569") (pin "1") (pinfunction "1_1") (pintype "passive"))
    )
    (net (code "63") (name "/RGMII2_TX_CTL") (class "Default")
      (node (ref "R580") (pin "1") (pinfunction "1_1") (pintype "passive"))
    )
    (net (code "64") (name "/SDIO_CLK") (class "Default")
      (node (ref "R562") (pin "1") (pinfunction "1_1") (pintype "passive"))
    )
    (net (code "65") (name "/SDIO_CLK_R") (class "Default")
      (node (ref "IC18") (pin "E29") (pinfunction "PS_MIO51_E29") (pintype "bidirectional"))
      (node (ref "R562") (pin "2") (pinfunction "2_2") (pintype "passive"))
    )
    (net (code "66") (name "/SDIO_CMD") (class "Default")
      (node (ref "R561") (pin "1") (pinfunction "1_1") (pintype "passive"))
    )
    (net (code "67") (name "/SDIO_CMD_R") (class "Default")
      (node (ref "IC18") (pin "F29") (pinfunction "PS_MIO50_F29") (pintype "bidirectional"))
      (node (ref "R561") (pin "2") (pinfunction "2_2") (pintype "passive"))
    )
    (net (code "68") (name "/SDIO_DAT0") (class "Default")
      (node (ref "R557") (pin "1") (pinfunction "1_1") (pintype "passive"))
    )
    (net (code "69") (name "/SDIO_DAT0_R") (class "Default")
      (node (ref "IC18") (pin "A29") (pinfunction "PS_MIO46_A29") (pintype "bidirectional"))
      (node (ref "R557") (pin "2") (pinfunction "2_2") (pintype "passive"))
    )
    (net (code "70") (name "/SDIO_DAT1") (class "Default")
      (node (ref "R558") (pin "1") (pinfunction "1_1") (pintype "passive"))
    )
    (net (code "71") (name "/SDIO_DAT1_R") (class "Default")
      (node (ref "IC18") (pin "C29") (pinfunction "PS_MIO47_C29") (pintype "bidirectional"))
      (node (ref "R558") (pin "2") (pinfunction "2_2") (pintype "passive"))
    )
    (net (code "72") (name "/SDIO_DAT2") (class "Default")
      (node (ref "R559") (pin "1") (pinfunction "1_1") (pintype "passive"))
    )
    (net (code "73") (name "/SDIO_DAT2_R") (class "Default")
      (node (ref "IC18") (pin "D29") (pinfunction "PS_MIO48_D29") (pintype "bidirectional"))
      (node (ref "R559") (pin "2") (pinfunction "2_2") (pintype "passive"))
    )
    (net (code "74") (name "/SDIO_DAT3") (class "Default")
      (node (ref "R560") (pin "1") (pinfunction "1_1") (pintype "passive"))
    )
    (net (code "75") (name "/SDIO_DAT3_R") (class "Default")
      (node (ref "IC18") (pin "B29") (pinfunction "PS_MIO49_B29") (pintype "bidirectional"))
      (node (ref "R560") (pin "2") (pinfunction "2_2") (pintype "passive"))
    )
    (net (code "76") (name "/SDIO_DETECT") (class "Default")
      (node (ref "IC18") (pin "G27") (pinfunction "PS_MIO45_G27") (pintype "bidirectional"))
    )
    (net (code "77") (name "/SDIO_SEL") (class "Default")
      (node (ref "IC18") (pin "B28") (pinfunction "PS_MIO39_B28") (pintype "bidirectional"))
    )
    (net (code "78") (name "/ULPI0_RST_B") (class "Default")
      (node (ref "R574") (pin "1") (pinfunction "1_1") (pintype "passive"))
      (node (ref "R578") (pin "1") (pinfunction "1_1") (pintype "passive"))
    )
    (net (code "79") (name "/USB_CLK") (class "Default")
      (node (ref "IC18") (pin "N26") (pinfunction "PS_MIO52_N26") (pintype "bidirectional"))
    )
    (net (code "80") (name "/USB_DATA0") (class "Default")
      (node (ref "R337") (pin "1") (pinfunction "1_1") (pintype "passive"))
    )
    (net (code "81") (name "/USB_DATA1") (class "Default")
      (node (ref "R339") (pin "1") (pinfunction "1_1") (pintype "passive"))
    )
    (net (code "82") (name "/USB_DATA2") (class "Default")
      (node (ref "R336") (pin "1") (pinfunction "1_1") (pintype "passive"))
    )
    (net (code "83") (name "/USB_DATA3") (class "Default")
      (node (ref "R341") (pin "1") (pinfunction "1_1") (pintype "passive"))
    )
    (net (code "84") (name "/USB_DATA4") (class "Default")
      (node (ref "R343") (pin "1") (pinfunction "1_1") (pintype "passive"))
    )
    (net (code "85") (name "/USB_DATA5") (class "Default")
      (node (ref "R346") (pin "1") (pinfunction "1_1") (pintype "passive"))
    )
    (net (code "86") (name "/USB_DATA6") (class "Default")
      (node (ref "R347") (pin "1") (pinfunction "1_1") (pintype "passive"))
    )
    (net (code "87") (name "/USB_DATA7") (class "Default")
      (node (ref "R348") (pin "1") (pinfunction "1_1") (pintype "passive"))
    )
    (net (code "88") (name "/USB_DIR") (class "Default")
      (node (ref "IC18") (pin "L25") (pinfunction "PS_MIO53_L25") (pintype "bidirectional"))
    )
    (net (code "89") (name "/USB_NXT") (class "Default")
      (node (ref "IC18") (pin "J25") (pinfunction "PS_MIO55_J25") (pintype "bidirectional"))
    )
    (net (code "90") (name "/USB_STP") (class "Default")
      (node (ref "R340") (pin "1") (pinfunction "1_1") (pintype "passive"))
    )
    (net (code "97") (name "GND") (class "Default")
      (node (ref "C467") (pin "1") (pinfunction "1_1") (pintype "passive"))
      (node (ref "C768") (pin "1") (pinfunction "1_1") (pintype "passive"))
      (node (ref "C770") (pin "1") (pinfunction "1_1") (pintype "passive"))
      (node (ref "C771") (pin "1") (pinfunction "1_1") (pintype "passive"))
      (node (ref "C772") (pin "1") (pinfunction "1_1") (pintype "passive"))
      (node (ref "C773") (pin "1") (pinfunction "1_1") (pintype "passive"))
      (node (ref "C774") (pin "1") (pinfunction "1_1") (pintype "passive"))
      (node (ref "C778") (pin "1") (pinfunction "1_1") (pintype "passive"))
      (node (ref "C779") (pin "1") (pinfunction "1_1") (pintype "passive"))
      (node (ref "C780") (pin "1") (pinfunction "1_1") (pintype "passive"))
      (node (ref "C866") (pin "1") (pinfunction "1_1") (pintype "passive"))
      (node (ref "C889") (pin "1") (pinfunction "1_1") (pintype "passive"))
      (node (ref "IC54") (pin "2") (pinfunction "GND_2") (pintype "power_in"))
      (node (ref "IC55") (pin "15") (pinfunction "~{OE}_15") (pintype "input"))
      (node (ref "IC55") (pin "8") (pinfunction "GND_8") (pintype "power_in"))
      (node (ref "IC56") (pin "10") (pinfunction "DIR1_10") (pintype "input"))
      (node (ref "IC56") (pin "2") (pinfunction "~{OE}_2") (pintype "input"))
      (node (ref "IC56") (pin "3") (pinfunction "GND_3") (pintype "power_in"))
      (node (ref "IC57") (pin "15") (pinfunction "~{OE}_15") (pintype "input"))
      (node (ref "IC57") (pin "8") (pinfunction "GND_8") (pintype "power_in"))
      (node (ref "IC59") (pin "15") (pinfunction "~{OE}_15") (pintype "input"))
      (node (ref "IC59") (pin "8") (pinfunction "GND_8") (pintype "power_in"))
      (node (ref "IC60") (pin "10") (pinfunction "VSS_10") (pintype "power_in"))
      (node (ref "IC61") (pin "10") (pinfunction "VSS_10") (pintype "power_in"))
      (node (ref "IC62") (pin "3") (pinfunction "GND_3") (pintype "power_in"))
      (node (ref "IC76") (pin "1") (pinfunction "DIR2_1") (pintype "input"))
      (node (ref "IC76") (pin "10") (pinfunction "DIR1_10") (pintype "input"))
      (node (ref "IC76") (pin "2") (pinfunction "~{OE}_2") (pintype "input"))
      (node (ref "IC76") (pin "3") (pinfunction "GND_3") (pintype "power_in"))
      (node (ref "R578") (pin "2") (pinfunction "2_2") (pintype "passive"))
    )
    (net (code "98") (name "Net-(IC18S-PS_MIO6)") (class "Default")
      (node (ref "IC18") (pin "W26") (pinfunction "PS_MIO6_W26") (pintype "bidirectional"))
      (node (ref "TP77") (pin "1") (pinfunction "1_1") (pintype "bidirectional"))
    )
    (net (code "99") (name "Net-(IC18S-PS_MIO7)") (class "Default")
      (node (ref "IC18") (pin "T26") (pinfunction "PS_MIO7_T26") (pintype "bidirectional"))
      (node (ref "TP78") (pin "1") (pinfunction "1_1") (pintype "bidirectional"))
    )
    (net (code "100") (name "Net-(IC18S-PS_MIO8)") (class "Default")
      (node (ref "IC18") (pin "U27") (pinfunction "PS_MIO8_U27") (pintype "bidirectional"))
      (node (ref "TP79") (pin "1") (pinfunction "1_1") (pintype "bidirectional"))
    )
    (net (code "101") (name "Net-(IC18S-PS_MIO9)") (class "Default")
      (node (ref "IC18") (pin "R27") (pinfunction "PS_MIO9_R27") (pintype "bidirectional"))
      (node (ref "TP80") (pin "1") (pinfunction "1_1") (pintype "bidirectional"))
    )
    (net (code "102") (name "Net-(IC18S-PS_MIO10)") (class "Default")
      (node (ref "IC18") (pin "V27") (pinfunction "PS_MIO10_V27") (pintype "bidirectional"))
      (node (ref "TP81") (pin "1") (pinfunction "1_1") (pintype "bidirectional"))
    )
    (net (code "103") (name "Net-(IC18S-PS_MIO11)") (class "Default")
      (node (ref "IC18") (pin "P28") (pinfunction "PS_MIO11_P28") (pintype "bidirectional"))
      (node (ref "TP82") (pin "1") (pinfunction "1_1") (pintype "bidirectional"))
    )
    (net (code "104") (name "Net-(IC18S-PS_MIO16)") (class "Default")
      (node (ref "IC18") (pin "R29") (pinfunction "PS_MIO16_R29") (pintype "bidirectional"))
      (node (ref "IC54") (pin "5") (pinfunction "A1_5") (pintype "bidirectional"))
      (node (ref "R546") (pin "1") (pinfunction "1_1") (pintype "passive"))
    )
    (net (code "105") (name "Net-(IC18S-PS_MIO17)") (class "Default")
      (node (ref "IC18") (pin "T29") (pinfunction "PS_MIO17_T29") (pintype "bidirectional"))
      (node (ref "IC54") (pin "4") (pinfunction "A2_4") (pintype "bidirectional"))
      (node (ref "R545") (pin "1") (pinfunction "1_1") (pintype "passive"))
    )
    (net (code "106") (name "Net-(IC18S-PS_MIO22)") (class "Default")
      (node (ref "IC18") (pin "Y28") (pinfunction "PS_MIO22_Y28") (pintype "bidirectional"))
      (node (ref "TP85") (pin "1") (pinfunction "1_1") (pintype "bidirectional"))
    )
    (net (code "107") (name "Net-(IC18S-PS_MIO23)") (class "Default")
      (node (ref "IC18") (pin "U29") (pinfunction "PS_MIO23_U29") (pintype "bidirectional"))
      (node (ref "TP86") (pin "1") (pinfunction "1_1") (pintype "bidirectional"))
    )
    (net (code "108") (name "Net-(IC18S-PS_MIO24)") (class "Default")
      (node (ref "IC18") (pin "Y29") (pinfunction "PS_MIO24_Y29") (pintype "bidirectional"))
      (node (ref "TP87") (pin "1") (pinfunction "1_1") (pintype "bidirectional"))
    )
    (net (code "109") (name "Net-(IC18S-PS_MIO25)") (class "Default")
      (node (ref "IC18") (pin "W29") (pinfunction "PS_MIO25_W29") (pintype "bidirectional"))
      (node (ref "TP88") (pin "1") (pinfunction "1_1") (pintype "bidirectional"))
    )
    (net (code "110") (name "Net-(IC18T-PS_MIO26)") (class "Default")
      (node (ref "IC18") (pin "G25") (pinfunction "PS_MIO26_G25") (pintype "bidirectional"))
      (node (ref "R551") (pin "2") (pinfunction "2_2") (pintype "passive"))
    )
    (net (code "111") (name "Net-(IC18T-PS_MIO27)") (class "Default")
      (node (ref "IC18") (pin "C25") (pinfunction "PS_MIO27_C25") (pintype "bidirectional"))
      (node (ref "R552") (pin "2") (pinfunction "2_2") (pintype "passive"))
    )
    (net (code "112") (name "Net-(IC18T-PS_MIO28)") (class "Default")
      (node (ref "IC18") (pin "F25") (pinfunction "PS_MIO28_F25") (pintype "bidirectional"))
      (node (ref "R553") (pin "2") (pinfunction "2_2") (pintype "passive"))
    )
    (net (code "113") (name "Net-(IC18T-PS_MIO29)") (class "Default")
      (node (ref "IC18") (pin "B25") (pinfunction "PS_MIO29_B25") (pintype "bidirectional"))
      (node (ref "R554") (pin "2") (pinfunction "2_2") (pintype "passive"))
    )
    (net (code "114") (name "Net-(IC18T-PS_MIO30)") (class "Default")
      (node (ref "IC18") (pin "D25") (pinfunction "PS_MIO30_D25") (pintype "bidirectional"))
      (node (ref "R555") (pin "2") (pinfunction "2_2") (pintype "passive"))
    )
    (net (code "115") (name "Net-(IC18T-PS_MIO31)") (class "Default")
      (node (ref "IC18") (pin "C26") (pinfunction "PS_MIO31_C26") (pintype "bidirectional"))
      (node (ref "R556") (pin "2") (pinfunction "2_2") (pintype "passive"))
    )
    (net (code "116") (name "Net-(IC18T-PS_MIO38)") (class "Default")
      (node (ref "IC18") (pin "E27") (pinfunction "PS_MIO38_E27") (pintype "bidirectional"))
      (node (ref "TP89") (pin "1") (pinfunction "1_1") (pintype "bidirectional"))
    )
    (net (code "117") (name "Net-(IC18T-PS_MIO43)") (class "Default")
      (node (ref "IC18") (pin "D28") (pinfunction "PS_MIO43_D28") (pintype "bidirectional"))
      (node (ref "TP90") (pin "1") (pinfunction "1_1") (pintype "bidirectional"))
    )
    (net (code "118") (name "Net-(IC18U-PS_MIO54)") (class "Default")
      (node (ref "IC18") (pin "M26") (pinfunction "PS_MIO54_M26") (pintype "bidirectional"))
      (node (ref "R336") (pin "2") (pinfunction "2_2") (pintype "passive"))
    )
    (net (code "119") (name "Net-(IC18U-PS_MIO56)") (class "Default")
      (node (ref "IC18") (pin "L26") (pinfunction "PS_MIO56_L26") (pintype "bidirectional"))
      (node (ref "R337") (pin "2") (pinfunction "2_2") (pintype "passive"))
    )
    (net (code "120") (name "Net-(IC18U-PS_MIO57)") (class "Default")
      (node (ref "IC18") (pin "H25") (pinfunction "PS_MIO57_H25") (pintype "bidirectional"))
      (node (ref "R339") (pin "2") (pinfunction "2_2") (pintype "passive"))
    )
    (net (code "121") (name "Net-(IC18U-PS_MIO58)") (class "Default")
      (node (ref "IC18") (pin "H26") (pinfunction "PS_MIO58_H26") (pintype "bidirectional"))
      (node (ref "R340") (pin "2") (pinfunction "2_2") (pintype "passive"))
    )
    (net (code "122") (name "Net-(IC18U-PS_MIO59)") (class "Default")
      (node (ref "IC18") (pin "H27") (pinfunction "PS_MIO59_H27") (pintype "bidirectional"))
      (node (ref "R341") (pin "2") (pinfunction "2_2") (pintype "passive"))
    )
    (net (code "123") (name "Net-(IC18U-PS_MIO60)") (class "Default")
      (node (ref "IC18") (pin "J26") (pinfunction "PS_MIO60_J26") (pintype "bidirectional"))
      (node (ref "R343") (pin "2") (pinfunction "2_2") (pintype "passive"))
    )
    (net (code "124") (name "Net-(IC18U-PS_MIO61)") (class "Default")
      (node (ref "IC18") (pin "G28") (pinfunction "PS_MIO61_G28") (pintype "bidirectional"))
      (node (ref "R346") (pin "2") (pinfunction "2_2") (pintype "passive"))
    )
    (net (code "125") (name "Net-(IC18U-PS_MIO62)") (class "Default")
      (node (ref "IC18") (pin "K26") (pinfunction "PS_MIO62_K26") (pintype "bidirectional"))
      (node (ref "R347") (pin "2") (pinfunction "2_2") (pintype "passive"))
    )
    (net (code "126") (name "Net-(IC18U-PS_MIO63)") (class "Default")
      (node (ref "IC18") (pin "G29") (pinfunction "PS_MIO63_G29") (pintype "bidirectional"))
      (node (ref "R348") (pin "2") (pinfunction "2_2") (pintype "passive"))
    )
    (net (code "127") (name "Net-(IC18U-PS_MIO64)") (class "Default")
      (node (ref "IC18") (pin "K27") (pinfunction "PS_MIO64_K27") (pintype "bidirectional"))
      (node (ref "R569") (pin "2") (pinfunction "2_2") (pintype "passive"))
    )
    (net (code "128") (name "Net-(IC18U-PS_MIO65)") (class "Default")
      (node (ref "IC18") (pin "L27") (pinfunction "PS_MIO65_L27") (pintype "bidirectional"))
      (node (ref "R570") (pin "2") (pinfunction "2_2") (pintype "passive"))
    )
    (net (code "129") (name "Net-(IC18U-PS_MIO66)") (class "Default")
      (node (ref "IC18") (pin "N27") (pinfunction "PS_MIO66_N27") (pintype "bidirectional"))
      (node (ref "R573") (pin "2") (pinfunction "2_2") (pintype "passive"))
    )
    (net (code "130") (name "Net-(IC18U-PS_MIO67)") (class "Default")
      (node (ref "IC18") (pin "J28") (pinfunction "PS_MIO67_J28") (pintype "bidirectional"))
      (node (ref "R575") (pin "2") (pinfunction "2_2") (pintype "passive"))
    )
    (net (code "131") (name "Net-(IC18U-PS_MIO68)") (class "Default")
      (node (ref "IC18") (pin "H29") (pinfunction "PS_MIO68_H29") (pintype "bidirectional"))
      (node (ref "R577") (pin "2") (pinfunction "2_2") (pintype "passive"))
    )
    (net (code "132") (name "Net-(IC18U-PS_MIO69)") (class "Default")
      (node (ref "IC18") (pin "M27") (pinfunction "PS_MIO69_M27") (pintype "bidirectional"))
      (node (ref "R580") (pin "2") (pinfunction "2_2") (pintype "passive"))
    )
    (net (code "133") (name "Net-(IC54-OE)") (class "Default")
      (node (ref "IC54") (pin "6") (pinfunction "OE_6") (pintype "input"))
      (node (ref "R544") (pin "1") (pinfunction "1_1") (pintype "passive"))
    )
    (net (code "134") (name "Net-(IC55-1A)") (class "Default")
      (node (ref "IC55") (pin "4") (pinfunction "1A_4") (pintype "output"))
      (node (ref "IC56") (pin "8") (pinfunction "A1_8") (pintype "bidirectional"))
    )
    (net (code "135") (name "Net-(IC55-2A)") (class "Default")
      (node (ref "IC55") (pin "7") (pinfunction "2A_7") (pintype "output"))
      (node (ref "IC56") (pin "9") (pinfunction "A2_9") (pintype "bidirectional"))
    )
    (net (code "136") (name "Net-(IC55-3A)") (class "Default")
      (node (ref "IC55") (pin "9") (pinfunction "3A_9") (pintype "output"))
      (node (ref "IC76") (pin "8") (pinfunction "A1_8") (pintype "bidirectional"))
    )
    (net (code "137") (name "Net-(IC55-4A)") (class "Default")
      (node (ref "IC55") (pin "12") (pinfunction "4A_12") (pintype "output"))
      (node (ref "IC76") (pin "9") (pinfunction "A2_9") (pintype "bidirectional"))
    )
    (net (code "138") (name "Net-(IC55-S)") (class "Default")
      (node (ref "IC55") (pin "1") (pinfunction "S_1") (pintype "input"))
      (node (ref "R547") (pin "1") (pinfunction "1_1") (pintype "passive"))
    )
    (net (code "139") (name "Net-(IC60-~{RESET})") (class "Default")
      (node (ref "IC60") (pin "3") (pinfunction "~{RESET}_3") (pintype "input"))
      (node (ref "R567") (pin "2") (pinfunction "2_2") (pintype "passive"))
    )
    (net (code "140") (name "Net-(IC61-~{RESET})") (class "Default")
      (node (ref "IC61") (pin "3") (pinfunction "~{RESET}_3") (pintype "input"))
      (node (ref "R579") (pin "2") (pinfunction "2_2") (pintype "passive"))
    )
    (net (code "141") (name "Net-(IC62-Y)") (class "Default")
      (node (ref "IC62") (pin "4") (pinfunction "Y_4") (pintype "output"))
      (node (ref "R574") (pin "2") (pinfunction "2_2") (pintype "passive"))
    )
    (net (code "142") (name "P1V8") (class "Default")
      (node (ref "C770") (pin "2") (pinfunction "2_2") (pintype "passive"))
      (node (ref "C772") (pin "2") (pinfunction "2_2") (pintype "passive"))
      (node (ref "C779") (pin "2") (pinfunction "2_2") (pintype "passive"))
      (node (ref "C780") (pin "2") (pinfunction "2_2") (pintype "passive"))
      (node (ref "C866") (pin "2") (pinfunction "2_2") (pintype "passive"))
      (node (ref "IC54") (pin "3") (pinfunction "Vcca_3") (pintype "power_in"))
      (node (ref "IC56") (pin "1") (pinfunction "DIR2_1") (pintype "input"))
      (node (ref "IC56") (pin "7") (pinfunction "VCCA_7") (pintype "power_in"))
      (node (ref "IC60") (pin "2") (pinfunction "VCC_2") (pintype "power_in"))
      (node (ref "IC61") (pin "2") (pinfunction "VCC_2") (pintype "power_in"))
      (node (ref "IC76") (pin "7") (pinfunction "VCCA_7") (pintype "power_in"))
      (node (ref "R544") (pin "2") (pinfunction "2_2") (pintype "passive"))
      (node (ref "R545") (pin "2") (pinfunction "2_2") (pintype "passive"))
      (node (ref "R546") (pin "2") (pinfunction "2_2") (pintype "passive"))
      (node (ref "R564") (pin "1") (pinfunction "1_1") (pintype "passive"))
      (node (ref "R565") (pin "2") (pinfunction "2_2") (pintype "passive"))
      (node (ref "R566") (pin "2") (pinfunction "2_2") (pintype "passive"))
      (node (ref "R567") (pin "1") (pinfunction "1_1") (pintype "passive"))
      (node (ref "R571") (pin "1") (pinfunction "1_1") (pintype "passive"))
      (node (ref "R572") (pin "2") (pinfunction "2_2") (pintype "passive"))
      (node (ref "R576") (pin "2") (pinfunction "2_2") (pintype "passive"))
      (node (ref "R579") (pin "1") (pinfunction "1_1") (pintype "passive"))
    )
    (net (code "143") (name "P3V3") (class "Default")
      (node (ref "C467") (pin "2") (pinfunction "2_2") (pintype "passive"))
      (node (ref "C768") (pin "2") (pinfunction "2_2") (pintype "passive"))
      (node (ref "C774") (pin "2") (pinfunction "2_2") (pintype "passive"))
      (node (ref "C778") (pin "2") (pinfunction "2_2") (pintype "passive"))
      (node (ref "IC55") (pin "16") (pinfunction "VCC_16") (pintype "power_in"))
      (node (ref "IC57") (pin "16") (pinfunction "VCC_16") (pintype "power_in"))
      (node (ref "IC59") (pin "16") (pinfunction "VCC_16") (pintype "power_in"))
      (node (ref "IC62") (pin "5") (pinfunction "VCC_5") (pintype "power_in"))
    )
    (net (code "144") (name "P3V3MP") (class "Default")
      (node (ref "C771") (pin "2") (pinfunction "2_2") (pintype "passive"))
      (node (ref "C773") (pin "2") (pinfunction "2_2") (pintype "passive"))
      (node (ref "C889") (pin "2") (pinfunction "2_2") (pintype "passive"))
      (node (ref "IC54") (pin "7") (pinfunction "Vccb_7") (pintype "power_in"))
      (node (ref "IC56") (pin "6") (pinfunction "VCCB_6") (pintype "power_in"))
      (node (ref "IC76") (pin "6") (pinfunction "VCCB_6") (pintype "power_in"))
    )
    (net (code "145") (name "unconnected-(IC18S-PS_MIO12-PadN29)") (class "Default")
      (node (ref "IC18") (pin "N29") (pinfunction "PS_MIO12_N29") (pintype "bidirectional"))
    )
    (net (code "146") (name "unconnected-(IC18S-PS_MIO13-PadR28)") (class "Default")
      (node (ref "IC18") (pin "R28") (pinfunction "PS_MIO13_R28") (pintype "bidirectional"))
    )
    (net (code "147") (name "unconnected-(IC18S-PS_MIO14-PadP29)") (class "Default")
      (node (ref "IC18") (pin "P29") (pinfunction "PS_MIO14_P29") (pintype "bidirectional"))
    )
    (net (code "148") (name "unconnected-(IC18S-PS_MIO15-PadU28)") (class "Default")
      (node (ref "IC18") (pin "U28") (pinfunction "PS_MIO15_U28") (pintype "bidirectional"))
    )
    (net (code "149") (name "unconnected-(IC18T-PS_MIO40-PadD26)") (class "Default")
      (node (ref "IC18") (pin "D26") (pinfunction "PS_MIO40_D26") (pintype "bidirectional"))
    )
    (net (code "150") (name "unconnected-(IC18T-PS_MIO41-PadC28)") (class "Default")
      (node (ref "IC18") (pin "C28") (pinfunction "PS_MIO41_C28") (pintype "bidirectional"))
    )
    (net (code "151") (name "unconnected-(IC18T-PS_MIO42-PadE28)") (class "Default")
      (node (ref "IC18") (pin "E28") (pinfunction "PS_MIO42_E28") (pintype "bidirectional"))
    )
    (net (code "152") (name "unconnected-(IC18T-PS_MIO44-PadF27)") (class "Default")
      (node (ref "IC18") (pin "F27") (pinfunction "PS_MIO44_F27") (pintype "bidirectional"))
    )
    (net (code "153") (name "unconnected-(IC57-3A-Pad9)") (class "Default")
      (node (ref "IC57") (pin "9") (pinfunction "3A_9") (pintype "output"))
    )
    (net (code "154") (name "unconnected-(IC57-3B1-Pad11)") (class "Default")
      (node (ref "IC57") (pin "11") (pinfunction "3B1_11") (pintype "input+no_connect"))
    )
    (net (code "155") (name "unconnected-(IC57-3B2-Pad10)") (class "Default")
      (node (ref "IC57") (pin "10") (pinfunction "3B2_10") (pintype "input+no_connect"))
    )
    (net (code "156") (name "unconnected-(IC57-4A-Pad12)") (class "Default")
      (node (ref "IC57") (pin "12") (pinfunction "4A_12") (pintype "output"))
    )
    (net (code "157") (name "unconnected-(IC57-4B1-Pad14)") (class "Default")
      (node (ref "IC57") (pin "14") (pinfunction "4B1_14") (pintype "input+no_connect"))
    )
    (net (code "158") (name "unconnected-(IC57-4B2-Pad13)") (class "Default")
      (node (ref "IC57") (pin "13") (pinfunction "4B2_13") (pintype "input+no_connect"))
    )
    (net (code "159") (name "unconnected-(IC60-DNU-Pad4)") (class "Default")
      (node (ref "IC60") (pin "4") (pinfunction "DNU_4") (pintype "passive"))
    )
    (net (code "160") (name "unconnected-(IC60-DNU-Pad5)") (class "Default")
      (node (ref "IC60") (pin "5") (pinfunction "DNU_5") (pintype "passive"))
    )
    (net (code "161") (name "unconnected-(IC60-DNU-Pad6)") (class "Default")
      (node (ref "IC60") (pin "6") (pinfunction "DNU_6") (pintype "passive"))
    )
    (net (code "162") (name "unconnected-(IC60-DNU-Pad11)") (class "Default")
      (node (ref "IC60") (pin "11") (pinfunction "DNU_11") (pintype "passive"))
    )
    (net (code "163") (name "unconnected-(IC60-DNU-Pad12)") (class "Default")
      (node (ref "IC60") (pin "12") (pinfunction "DNU_12") (pintype "passive"))
    )
    (net (code "164") (name "unconnected-(IC60-DNU-Pad13)") (class "Default")
      (node (ref "IC60") (pin "13") (pinfunction "DNU_13") (pintype "passive"))
    )
    (net (code "165") (name "unconnected-(IC60-DNU-Pad14)") (class "Default")
      (node (ref "IC60") (pin "14") (pinfunction "DNU_14") (pintype "passive"))
    )
    (net (code "166") (name "unconnected-(IC61-DNU-Pad4)") (class "Default")
      (node (ref "IC61") (pin "4") (pinfunction "DNU_4") (pintype "passive"))
    )
    (net (code "167") (name "unconnected-(IC61-DNU-Pad5)") (class "Default")
      (node (ref "IC61") (pin "5") (pinfunction "DNU_5") (pintype "passive"))
    )
    (net (code "168") (name "unconnected-(IC61-DNU-Pad6)") (class "Default")
      (node (ref "IC61") (pin "6") (pinfunction "DNU_6") (pintype "passive"))
    )
    (net (code "169") (name "unconnected-(IC61-DNU-Pad11)") (class "Default")
      (node (ref "IC61") (pin "11") (pinfunction "DNU_11") (pintype "passive"))
    )
    (net (code "170") (name "unconnected-(IC61-DNU-Pad12)") (class "Default")
      (node (ref "IC61") (pin "12") (pinfunction "DNU_12") (pintype "passive"))
    )
    (net (code "171") (name "unconnected-(IC61-DNU-Pad13)") (class "Default")
      (node (ref "IC61") (pin "13") (pinfunction "DNU_13") (pintype "passive"))
    )
    (net (code "172") (name "unconnected-(IC61-DNU-Pad14)") (class "Default")
      (node (ref "IC61") (pin "14") (pinfunction "DNU_14") (pintype "passive"))
    )
  )
)
